# stabilizator_nap.net
KiCad netlist of a schematic drawn in Altium Designer
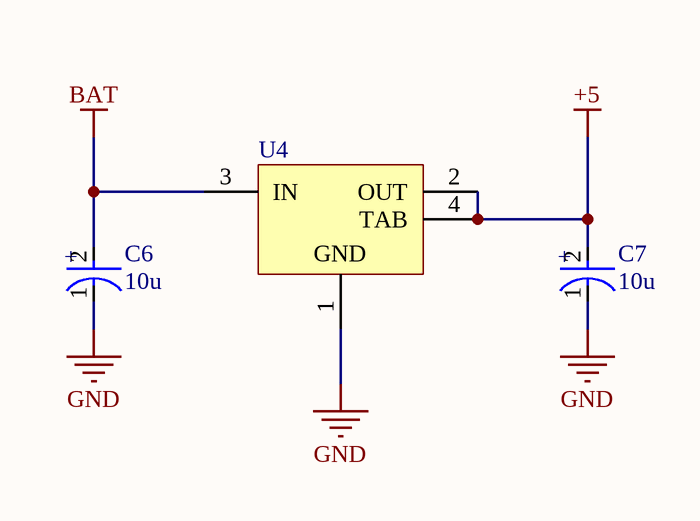
[diagram p0: stabilizator nap..SchDoc]

(export (version "E")
  (design (tool "Eeschema 10.0.6"))
  (components
    (comp (ref "C6")
      (value "10u")
      (footprint "FP-TAJP-MFG")
      (description "10uF 10V  ±20% 6Ω 0805  SMD Tantalum Capacitor")
      (fields (field (name "TOLERANCE") "20%") (field (name "VOLTAGE") "10V"))
      (libsource (lib "Altium Content Vault") (part "a00bbbee19879c290e62620ae7e47b1"))
    )
    (comp (ref "C7")
      (value "10u")
      (footprint "FP-TAJP-MFG")
      (description "10uF 10V  ±20% 6Ω 0805  SMD Tantalum Capacitor")
      (fields (field (name "TOLERANCE") "20%") (field (name "VOLTAGE") "10V"))
      (libsource (lib "Altium Content Vault") (part "a00bbbee19879c290e62620ae7e47b1"))
    )
    (comp (ref "U4")
      (value "LM1117MPX-5.0/NOPB")
      (footprint "DCY0004A_L")
      (description "800mA Low-Dropout Linear Regulator, 4-pin SOT-223, Pb-Free")
      (fields (field (name "MANUFACTURER") "Texas Instruments"))
      (libsource (lib "Altium Content Vault") (part "PM-REG-LM1086-SOT4"))
    )
  )
  (nets
    (net (code "1") (name "+5") (class "Default")
      (node (ref "C7") (pin "2") (pinfunction "A_2") (pintype "passive"))
      (node (ref "U4") (pin "2") (pinfunction "OUT_2") (pintype "power_in"))
      (node (ref "U4") (pin "4") (pinfunction "TAB_4") (pintype "power_in"))
    )
    (net (code "2") (name "BAT") (class "Default")
      (node (ref "C6") (pin "2") (pinfunction "A_2") (pintype "passive"))
      (node (ref "U4") (pin "3") (pinfunction "IN_3") (pintype "power_in"))
    )
    (net (code "3") (name "GND") (class "Default")
      (node (ref "C6") (pin "1") (pinfunction "C_1") (pintype "passive"))
      (node (ref "C7") (pin "1") (pinfunction "C_1") (pintype "passive"))
      (node (ref "U4") (pin "1") (pinfunction "GND_1") (pintype "power_in"))
    )
  )
)
